# V-00634-00.net
KiCad netlist of a schematic drawn in EAGLE
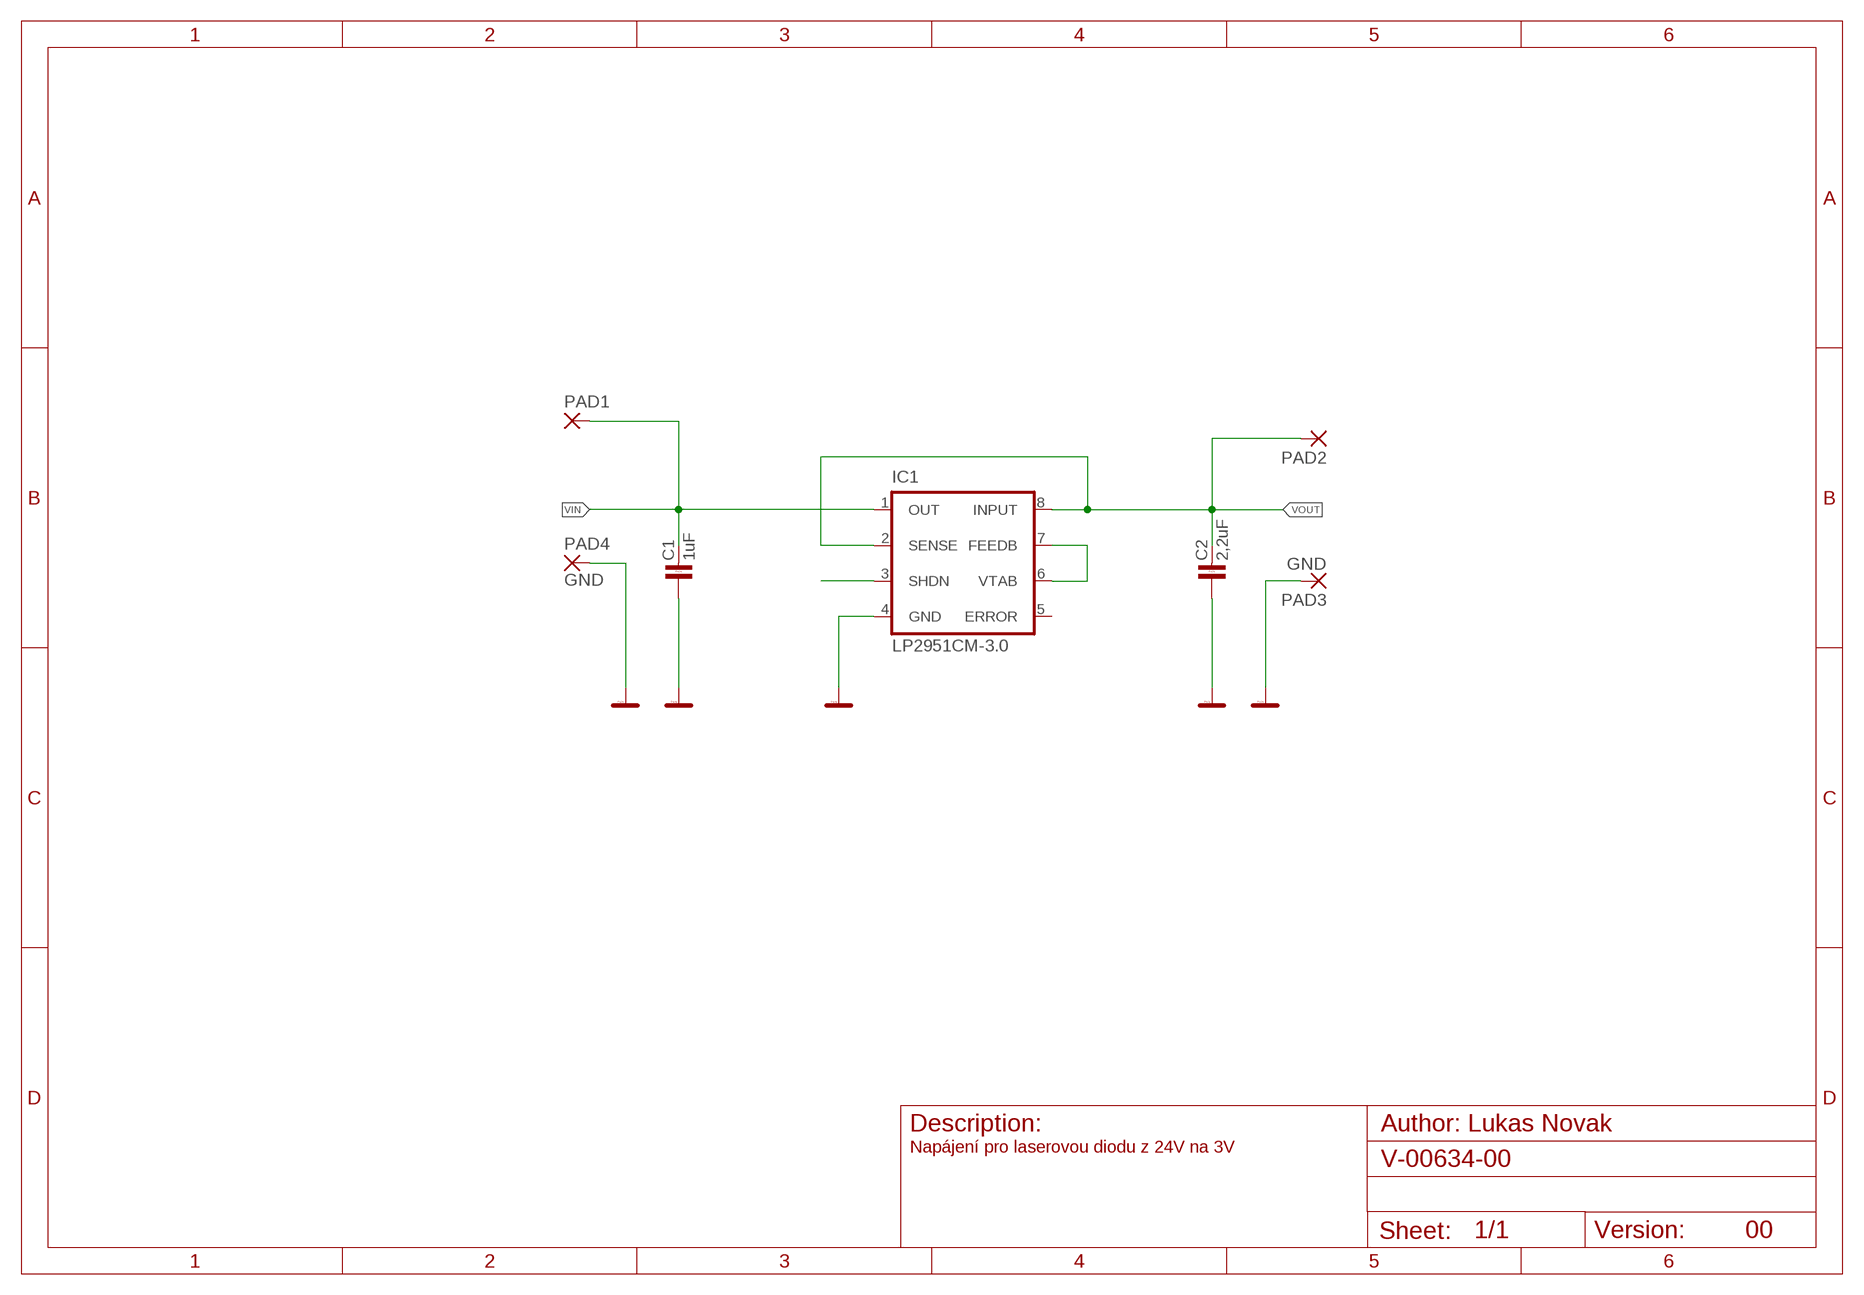
[diagram p0: schematic, sheet 1]

(export (version "E")
  (design (tool "Eeschema 10.0.6"))
  (components
    (comp (ref "C1")
      (value "1uF")
      (footprint "eagle-import:1206")
      (libsource (lib "eagle-import") (part "C-KER_1206"))
    )
    (comp (ref "C2")
      (value "2,2uF")
      (footprint "eagle-import:1206")
      (libsource (lib "eagle-import") (part "C-KER_1206"))
    )
    (comp (ref "IC1")
      (value "LP2951CM-3.0")
      (footprint "eagle-import:SO-08")
      (libsource (lib "eagle-import") (part "LP2951?CM-3.0"))
    )
    (comp (ref "PAD1")
      (value "2,54/0,9")
      (footprint "eagle-import:2,54_0,9")
      (libsource (lib "eagle-import") (part "2,54/0,9"))
    )
    (comp (ref "PAD2")
      (value "2,54/0,9")
      (footprint "eagle-import:2,54_0,9")
      (libsource (lib "eagle-import") (part "2,54/0,9"))
    )
    (comp (ref "PAD3")
      (value "GND")
      (footprint "eagle-import:2,54_0,9")
      (libsource (lib "eagle-import") (part "2,54/0,9"))
    )
    (comp (ref "PAD4")
      (value "GND")
      (footprint "eagle-import:2,54_0,9")
      (libsource (lib "eagle-import") (part "2,54/0,9"))
    )
  )
  (nets
    (net (code "1") (name "GND") (class "Default")
      (node (ref "C1") (pin "1") (pinfunction "1_1") (pintype "passive"))
      (node (ref "C2") (pin "1") (pinfunction "1_1") (pintype "passive"))
      (node (ref "IC1") (pin "4") (pinfunction "GND_4") (pintype "power_in"))
      (node (ref "PAD3") (pin "1") (pinfunction "P_1") (pintype "passive"))
      (node (ref "PAD4") (pin "1") (pinfunction "P_1") (pintype "passive"))
    )
    (net (code "2") (name "Net-(IC1-FEEDB)") (class "Default")
      (node (ref "IC1") (pin "6") (pinfunction "VTAB_6") (pintype "input"))
      (node (ref "IC1") (pin "7") (pinfunction "FEEDB_7") (pintype "output"))
    )
    (net (code "3") (name "VIN") (class "Default")
      (node (ref "C1") (pin "2") (pinfunction "2_2") (pintype "passive"))
      (node (ref "IC1") (pin "1") (pinfunction "OUT_1") (pintype "output"))
      (node (ref "PAD1") (pin "1") (pinfunction "P_1") (pintype "passive"))
    )
    (net (code "4") (name "VOUT") (class "Default")
      (node (ref "C2") (pin "2") (pinfunction "2_2") (pintype "passive"))
      (node (ref "IC1") (pin "2") (pinfunction "SENSE_2") (pintype "input"))
      (node (ref "IC1") (pin "8") (pinfunction "INPUT_8") (pintype "passive"))
      (node (ref "PAD2") (pin "1") (pinfunction "P_1") (pintype "passive"))
    )
    (net (code "5") (name "unconnected-(IC1-ERROR-Pad5)") (class "Default")
      (node (ref "IC1") (pin "5") (pinfunction "ERROR_5") (pintype "output"))
    )
    (net (code "6") (name "unconnected-(IC1-SHDN-Pad3)") (class "Default")
      (node (ref "IC1") (pin "3") (pinfunction "SHDN_3") (pintype "input"))
    )
  )
)
